# Motor.net
KiCad netlist of a schematic drawn in Altium Designer
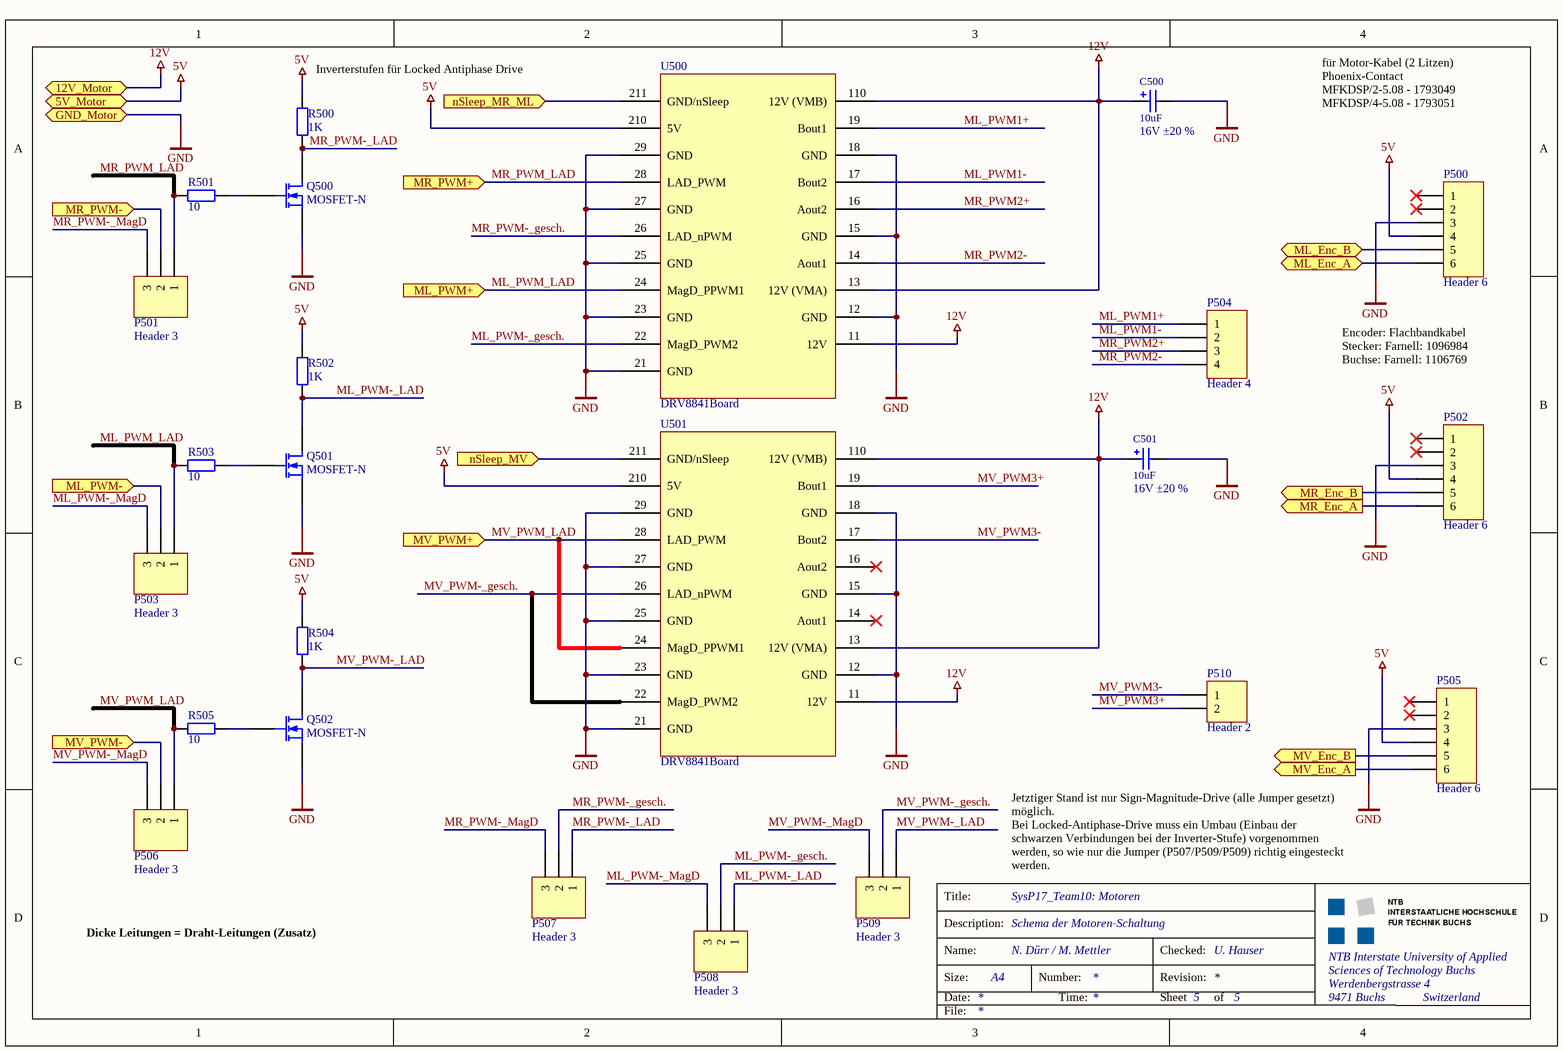
[diagram p0: Motor.SchDoc]

(export (version "E")
  (design (tool "Eeschema 10.0.6"))
  (components
    (comp (ref "C500")
      (value "10uF")
      (footprint "CDE_CAP AVE CODE D_H")
      (description "Aluminum Electrolytic Capacitors for Filtering and Bypass, 47uF, 16V")
      (fields
        (field (name "MANUFACTURER") "Cornell Dubilier")
        (field (name "VALUEADDON") "16V ±20 %")
        (field (name "Comment") "AVE476M16D16T-F")
        (field (name "PUBLISHER") "Stefan Ursella, M.Eng")
      )
      (libsource (lib "Motortreiber") (part "CDE_AVE476M16D16T-F_AVE CODE D"))
    )
    (comp (ref "C501")
      (value "10uF")
      (footprint "CDE_CAP AVE CODE D_H")
      (description "Aluminum Electrolytic Capacitors for Filtering and Bypass, 47uF, 16V")
      (fields
        (field (name "MANUFACTURER") "Cornell Dubilier")
        (field (name "VALUEADDON") "16V ±20 %")
        (field (name "Comment") "AVE476M16D16T-F")
        (field (name "PUBLISHER") "Stefan Ursella, M.Eng")
      )
      (libsource (lib "Motortreiber") (part "CDE_AVE476M16D16T-F_AVE CODE D"))
    )
    (comp (ref "P500")
      (value "Header 6")
      (footprint "HDR2X3")
      (description "Header, 6-Pin")
      (fields (field (name "PUBLISHER") "Altium Limited"))
      (libsource (lib "Miscellaneous Connectors") (part "Header 6"))
    )
    (comp (ref "P501")
      (value "Header 3")
      (footprint "HDR1X3")
      (description "Header, 3-Pin")
      (fields (field (name "PUBLISHER") "Altium Limited"))
      (libsource (lib "Miscellaneous Connectors") (part "Header 3"))
    )
    (comp (ref "P502")
      (value "Header 6")
      (footprint "HDR2X3")
      (description "Header, 6-Pin")
      (fields (field (name "PUBLISHER") "Altium Limited"))
      (libsource (lib "Miscellaneous Connectors") (part "Header 6"))
    )
    (comp (ref "P503")
      (value "Header 3")
      (footprint "HDR1X3")
      (description "Header, 3-Pin")
      (fields (field (name "PUBLISHER") "Altium Limited"))
      (libsource (lib "Miscellaneous Connectors") (part "Header 3"))
    )
    (comp (ref "P504")
      (value "Header 4")
      (footprint "Connector_4Header")
      (description "Header, 4-Pin")
      (fields (field (name "PUBLISHER") "Altium Limited"))
      (libsource (lib "Miscellaneous Connectors") (part "Header 4"))
    )
    (comp (ref "P505")
      (value "Header 6")
      (footprint "HDR2X3")
      (description "Header, 6-Pin")
      (fields (field (name "PUBLISHER") "Altium Limited"))
      (libsource (lib "Miscellaneous Connectors") (part "Header 6"))
    )
    (comp (ref "P506")
      (value "Header 3")
      (footprint "HDR1X3")
      (description "Header, 3-Pin")
      (fields (field (name "PUBLISHER") "Altium Limited"))
      (libsource (lib "Miscellaneous Connectors") (part "Header 3"))
    )
    (comp (ref "P507")
      (value "Header 3")
      (footprint "HDR1X3")
      (description "Header, 3-Pin")
      (fields (field (name "PUBLISHER") "Altium Limited"))
      (libsource (lib "Miscellaneous Connectors") (part "Header 3"))
    )
    (comp (ref "P508")
      (value "Header 3")
      (footprint "HDR1X3")
      (description "Header, 3-Pin")
      (fields (field (name "PUBLISHER") "Altium Limited"))
      (libsource (lib "Miscellaneous Connectors") (part "Header 3"))
    )
    (comp (ref "P509")
      (value "Header 3")
      (footprint "HDR1X3")
      (description "Header, 3-Pin")
      (fields (field (name "PUBLISHER") "Altium Limited"))
      (libsource (lib "Miscellaneous Connectors") (part "Header 3"))
    )
    (comp (ref "P510")
      (value "Header 2")
      (footprint "Connector_2Header")
      (description "Header, 2-Pin")
      (fields (field (name "PUBLISHER") "Altium Limited"))
      (libsource (lib "Miscellaneous Connectors") (part "Header 2"))
    )
    (comp (ref "Q500")
      (value "MOSFET-N")
      (footprint "SOT23-3")
      (description "N-Channel MOSFET")
      (fields (field (name "PUBLISHER") "Altium Limited"))
      (libsource (lib "Miscellaneous Devices") (part "MOSFET-N"))
    )
    (comp (ref "Q501")
      (value "MOSFET-N")
      (footprint "SOT23-3")
      (description "N-Channel MOSFET")
      (fields (field (name "PUBLISHER") "Altium Limited"))
      (libsource (lib "Miscellaneous Devices") (part "MOSFET-N"))
    )
    (comp (ref "Q502")
      (value "MOSFET-N")
      (footprint "SOT23-3")
      (description "N-Channel MOSFET")
      (fields (field (name "PUBLISHER") "Altium Limited"))
      (libsource (lib "Miscellaneous Devices") (part "MOSFET-N"))
    )
    (comp (ref "R500")
      (value "1K")
      (footprint "GEN_R0805_H")
      (description "generic resistor")
      (fields
        (field (name "MANUFACTURER") "Tbd")
        (field (name "Comment") "Generic")
        (field (name "PUBLISHER") "Altium Limited")
      )
      (libsource (lib "") (part "GEN_R_2_1"))
    )
    (comp (ref "R501")
      (value "10")
      (footprint "GEN_R0805_H")
      (description "generic resistor")
      (fields
        (field (name "MANUFACTURER") "Tbd")
        (field (name "Comment") "Generic")
        (field (name "PUBLISHER") "Altium Limited")
      )
      (libsource (lib "Motortreiber") (part "GEN_R_2"))
    )
    (comp (ref "R502")
      (value "1K")
      (footprint "GEN_R0805_H")
      (description "generic resistor")
      (fields
        (field (name "MANUFACTURER") "Tbd")
        (field (name "Comment") "Generic")
        (field (name "PUBLISHER") "Altium Limited")
      )
      (libsource (lib "") (part "GEN_R_2_1"))
    )
    (comp (ref "R503")
      (value "10")
      (footprint "GEN_R0805_H")
      (description "generic resistor")
      (fields
        (field (name "MANUFACTURER") "Tbd")
        (field (name "Comment") "Generic")
        (field (name "PUBLISHER") "Altium Limited")
      )
      (libsource (lib "Motortreiber") (part "GEN_R_2"))
    )
    (comp (ref "R504")
      (value "1K")
      (footprint "GEN_R0805_H")
      (description "generic resistor")
      (fields
        (field (name "MANUFACTURER") "Tbd")
        (field (name "Comment") "Generic")
        (field (name "PUBLISHER") "Altium Limited")
      )
      (libsource (lib "") (part "GEN_R_2_1"))
    )
    (comp (ref "R505")
      (value "10")
      (footprint "GEN_R0805_H")
      (description "generic resistor")
      (fields
        (field (name "MANUFACTURER") "Tbd")
        (field (name "Comment") "Generic")
        (field (name "PUBLISHER") "Altium Limited")
      )
      (libsource (lib "Motortreiber") (part "GEN_R_2"))
    )
    (comp (ref "U500")
      (value "DRV8841Board")
      (footprint "DRV8841_Board")
      (libsource (lib "Motortreiber") (part "DRV8841_Board"))
    )
    (comp (ref "U501")
      (value "DRV8841Board")
      (footprint "DRV8841_Board")
      (libsource (lib "Motortreiber") (part "DRV8841_Board"))
    )
  )
  (nets
    (net (code "1") (name "/ML_Enc_A") (class "Default")
      (node (ref "P500") (pin "6") (pinfunction "6_6") (pintype "passive"))
    )
    (net (code "2") (name "/ML_Enc_B") (class "Default")
      (node (ref "P500") (pin "5") (pinfunction "5_5") (pintype "passive"))
    )
    (net (code "3") (name "/ML_PWM-") (class "Default")
      (node (ref "P503") (pin "2") (pinfunction "2_2") (pintype "passive"))
    )
    (net (code "4") (name "/ML_PWM-_LAD") (class "Default")
      (node (ref "P508") (pin "1") (pinfunction "1_1") (pintype "passive"))
      (node (ref "Q501") (pin "3") (pinfunction "D_3") (pintype "passive"))
      (node (ref "R502") (pin "1") (pinfunction "1_1") (pintype "passive"))
    )
    (net (code "5") (name "/ML_PWM-_MagD") (class "Default")
      (node (ref "P503") (pin "3") (pinfunction "3_3") (pintype "passive"))
      (node (ref "P508") (pin "3") (pinfunction "3_3") (pintype "passive"))
    )
    (net (code "6") (name "/ML_PWM-_gesch.") (class "Default")
      (node (ref "P508") (pin "2") (pinfunction "2_2") (pintype "passive"))
      (node (ref "U500") (pin "22") (pinfunction "MagD_PWM2_22") (pintype "passive"))
    )
    (net (code "7") (name "/ML_PWM1+") (class "Default")
      (node (ref "P504") (pin "1") (pinfunction "1_1") (pintype "passive"))
      (node (ref "U500") (pin "19") (pinfunction "Bout1_19") (pintype "passive"))
    )
    (net (code "8") (name "/ML_PWM1-") (class "Default")
      (node (ref "P504") (pin "2") (pinfunction "2_2") (pintype "passive"))
      (node (ref "U500") (pin "17") (pinfunction "Bout2_17") (pintype "passive"))
    )
    (net (code "9") (name "/ML_PWM_LAD") (class "Default")
      (node (ref "P503") (pin "1") (pinfunction "1_1") (pintype "passive"))
      (node (ref "R503") (pin "2") (pinfunction "2_2") (pintype "passive"))
      (node (ref "U500") (pin "24") (pinfunction "MagD_PPWM1_24") (pintype "passive"))
    )
    (net (code "10") (name "/MR_Enc_A") (class "Default")
      (node (ref "P502") (pin "6") (pinfunction "6_6") (pintype "passive"))
    )
    (net (code "11") (name "/MR_Enc_B") (class "Default")
      (node (ref "P502") (pin "5") (pinfunction "5_5") (pintype "passive"))
    )
    (net (code "12") (name "/MR_PWM-") (class "Default")
      (node (ref "P501") (pin "2") (pinfunction "2_2") (pintype "passive"))
    )
    (net (code "13") (name "/MR_PWM-_LAD") (class "Default")
      (node (ref "P507") (pin "1") (pinfunction "1_1") (pintype "passive"))
      (node (ref "Q500") (pin "3") (pinfunction "D_3") (pintype "passive"))
      (node (ref "R500") (pin "1") (pinfunction "1_1") (pintype "passive"))
    )
    (net (code "14") (name "/MR_PWM-_MagD") (class "Default")
      (node (ref "P501") (pin "3") (pinfunction "3_3") (pintype "passive"))
      (node (ref "P507") (pin "3") (pinfunction "3_3") (pintype "passive"))
    )
    (net (code "15") (name "/MR_PWM-_gesch.") (class "Default")
      (node (ref "P507") (pin "2") (pinfunction "2_2") (pintype "passive"))
      (node (ref "U500") (pin "26") (pinfunction "LAD_nPWM_26") (pintype "passive"))
    )
    (net (code "16") (name "/MR_PWM2+") (class "Default")
      (node (ref "P504") (pin "3") (pinfunction "3_3") (pintype "passive"))
      (node (ref "U500") (pin "16") (pinfunction "Aout2_16") (pintype "passive"))
    )
    (net (code "17") (name "/MR_PWM2-") (class "Default")
      (node (ref "P504") (pin "4") (pinfunction "4_4") (pintype "passive"))
      (node (ref "U500") (pin "14") (pinfunction "Aout1_14") (pintype "passive"))
    )
    (net (code "18") (name "/MR_PWM_LAD") (class "Default")
      (node (ref "P501") (pin "1") (pinfunction "1_1") (pintype "passive"))
      (node (ref "R501") (pin "2") (pinfunction "2_2") (pintype "passive"))
      (node (ref "U500") (pin "28") (pinfunction "LAD_PWM_28") (pintype "passive"))
    )
    (net (code "19") (name "/MV_Enc_A") (class "Default")
      (node (ref "P505") (pin "6") (pinfunction "6_6") (pintype "passive"))
    )
    (net (code "20") (name "/MV_Enc_B") (class "Default")
      (node (ref "P505") (pin "5") (pinfunction "5_5") (pintype "passive"))
    )
    (net (code "21") (name "/MV_PWM-") (class "Default")
      (node (ref "P506") (pin "2") (pinfunction "2_2") (pintype "passive"))
    )
    (net (code "22") (name "/MV_PWM-_LAD") (class "Default")
      (node (ref "P509") (pin "1") (pinfunction "1_1") (pintype "passive"))
      (node (ref "Q502") (pin "3") (pinfunction "D_3") (pintype "passive"))
      (node (ref "R504") (pin "1") (pinfunction "1_1") (pintype "passive"))
    )
    (net (code "23") (name "/MV_PWM-_MagD") (class "Default")
      (node (ref "P506") (pin "3") (pinfunction "3_3") (pintype "passive"))
      (node (ref "P509") (pin "3") (pinfunction "3_3") (pintype "passive"))
    )
    (net (code "24") (name "/MV_PWM-_gesch.") (class "Default")
      (node (ref "P509") (pin "2") (pinfunction "2_2") (pintype "passive"))
      (node (ref "U501") (pin "22") (pinfunction "MagD_PWM2_22") (pintype "passive"))
      (node (ref "U501") (pin "26") (pinfunction "LAD_nPWM_26") (pintype "passive"))
    )
    (net (code "25") (name "/MV_PWM3+") (class "Default")
      (node (ref "P510") (pin "2") (pinfunction "2_2") (pintype "passive"))
      (node (ref "U501") (pin "19") (pinfunction "Bout1_19") (pintype "passive"))
    )
    (net (code "26") (name "/MV_PWM3-") (class "Default")
      (node (ref "P510") (pin "1") (pinfunction "1_1") (pintype "passive"))
      (node (ref "U501") (pin "17") (pinfunction "Bout2_17") (pintype "passive"))
    )
    (net (code "27") (name "/MV_PWM_LAD") (class "Default")
      (node (ref "P506") (pin "1") (pinfunction "1_1") (pintype "passive"))
      (node (ref "R505") (pin "2") (pinfunction "2_2") (pintype "passive"))
      (node (ref "U501") (pin "24") (pinfunction "MagD_PPWM1_24") (pintype "passive"))
      (node (ref "U501") (pin "28") (pinfunction "LAD_PWM_28") (pintype "passive"))
    )
    (net (code "28") (name "/nSleep_MR_ML") (class "Default")
      (node (ref "U500") (pin "211") (pinfunction "GND/nSleep_211") (pintype "passive"))
    )
    (net (code "29") (name "/nSleep_MV") (class "Default")
      (node (ref "U501") (pin "211") (pinfunction "GND/nSleep_211") (pintype "passive"))
    )
    (net (code "30") (name "5V") (class "Default")
      (node (ref "P500") (pin "4") (pinfunction "4_4") (pintype "passive"))
      (node (ref "P502") (pin "4") (pinfunction "4_4") (pintype "passive"))
      (node (ref "P505") (pin "4") (pinfunction "4_4") (pintype "passive"))
      (node (ref "R500") (pin "2") (pinfunction "2_2") (pintype "passive"))
      (node (ref "R502") (pin "2") (pinfunction "2_2") (pintype "passive"))
      (node (ref "R504") (pin "2") (pinfunction "2_2") (pintype "passive"))
      (node (ref "U500") (pin "210") (pinfunction "5V_210") (pintype "passive"))
      (node (ref "U501") (pin "210") (pinfunction "5V_210") (pintype "passive"))
    )
    (net (code "31") (name "12V") (class "Default")
      (node (ref "C500") (pin "1") (pinfunction "Pos_1") (pintype "passive"))
      (node (ref "C501") (pin "1") (pinfunction "Pos_1") (pintype "passive"))
      (node (ref "U500") (pin "11") (pinfunction "12V_11") (pintype "passive"))
      (node (ref "U500") (pin "110") (pinfunction "12V_(VMB)_110") (pintype "passive"))
      (node (ref "U500") (pin "13") (pinfunction "12V_(VMA)_13") (pintype "passive"))
      (node (ref "U501") (pin "11") (pinfunction "12V_11") (pintype "passive"))
      (node (ref "U501") (pin "110") (pinfunction "12V_(VMB)_110") (pintype "passive"))
      (node (ref "U501") (pin "13") (pinfunction "12V_(VMA)_13") (pintype "passive"))
    )
    (net (code "32") (name "GND") (class "Default")
      (node (ref "C500") (pin "2") (pinfunction "Neg_2") (pintype "passive"))
      (node (ref "C501") (pin "2") (pinfunction "Neg_2") (pintype "passive"))
      (node (ref "P500") (pin "3") (pinfunction "3_3") (pintype "passive"))
      (node (ref "P502") (pin "3") (pinfunction "3_3") (pintype "passive"))
      (node (ref "P505") (pin "3") (pinfunction "3_3") (pintype "passive"))
      (node (ref "Q500") (pin "2") (pinfunction "S_2") (pintype "passive"))
      (node (ref "Q501") (pin "2") (pinfunction "S_2") (pintype "passive"))
      (node (ref "Q502") (pin "2") (pinfunction "S_2") (pintype "passive"))
      (node (ref "U500") (pin "12") (pinfunction "GND_12") (pintype "passive"))
      (node (ref "U500") (pin "15") (pinfunction "GND_15") (pintype "passive"))
      (node (ref "U500") (pin "18") (pinfunction "GND_18") (pintype "passive"))
      (node (ref "U500") (pin "21") (pinfunction "GND_21") (pintype "passive"))
      (node (ref "U500") (pin "23") (pinfunction "GND_23") (pintype "passive"))
      (node (ref "U500") (pin "25") (pinfunction "GND_25") (pintype "passive"))
      (node (ref "U500") (pin "27") (pinfunction "GND_27") (pintype "passive"))
      (node (ref "U500") (pin "29") (pinfunction "GND_29") (pintype "passive"))
      (node (ref "U501") (pin "12") (pinfunction "GND_12") (pintype "passive"))
      (node (ref "U501") (pin "15") (pinfunction "GND_15") (pintype "passive"))
      (node (ref "U501") (pin "18") (pinfunction "GND_18") (pintype "passive"))
      (node (ref "U501") (pin "21") (pinfunction "GND_21") (pintype "passive"))
      (node (ref "U501") (pin "23") (pinfunction "GND_23") (pintype "passive"))
      (node (ref "U501") (pin "25") (pinfunction "GND_25") (pintype "passive"))
      (node (ref "U501") (pin "27") (pinfunction "GND_27") (pintype "passive"))
      (node (ref "U501") (pin "29") (pinfunction "GND_29") (pintype "passive"))
    )
    (net (code "33") (name "Net-(Q500-G)") (class "Default")
      (node (ref "Q500") (pin "1") (pinfunction "G_1") (pintype "passive"))
      (node (ref "R501") (pin "1") (pinfunction "1_1") (pintype "passive"))
    )
    (net (code "34") (name "Net-(Q501-G)") (class "Default")
      (node (ref "Q501") (pin "1") (pinfunction "G_1") (pintype "passive"))
      (node (ref "R503") (pin "1") (pinfunction "1_1") (pintype "passive"))
    )
    (net (code "35") (name "Net-(Q502-G)") (class "Default")
      (node (ref "Q502") (pin "1") (pinfunction "G_1") (pintype "passive"))
      (node (ref "R505") (pin "1") (pinfunction "1_1") (pintype "passive"))
    )
    (net (code "36") (name "unconnected-(P500-Pad1)") (class "Default")
      (node (ref "P500") (pin "1") (pinfunction "1_1") (pintype "passive+no_connect"))
    )
    (net (code "37") (name "unconnected-(P500-Pad2)") (class "Default")
      (node (ref "P500") (pin "2") (pinfunction "2_2") (pintype "passive+no_connect"))
    )
    (net (code "38") (name "unconnected-(P502-Pad1)") (class "Default")
      (node (ref "P502") (pin "1") (pinfunction "1_1") (pintype "passive+no_connect"))
    )
    (net (code "39") (name "unconnected-(P502-Pad2)") (class "Default")
      (node (ref "P502") (pin "2") (pinfunction "2_2") (pintype "passive+no_connect"))
    )
    (net (code "40") (name "unconnected-(P505-Pad1)") (class "Default")
      (node (ref "P505") (pin "1") (pinfunction "1_1") (pintype "passive+no_connect"))
    )
    (net (code "41") (name "unconnected-(P505-Pad2)") (class "Default")
      (node (ref "P505") (pin "2") (pinfunction "2_2") (pintype "passive+no_connect"))
    )
    (net (code "42") (name "unconnected-(U501-Aout1-Pad14)") (class "Default")
      (node (ref "U501") (pin "14") (pinfunction "Aout1_14") (pintype "passive+no_connect"))
    )
    (net (code "43") (name "unconnected-(U501-Aout2-Pad16)") (class "Default")
      (node (ref "U501") (pin "16") (pinfunction "Aout2_16") (pintype "passive+no_connect"))
    )
  )
)
